# DS1077_breakout.net
KiCad netlist of a schematic drawn in EAGLE
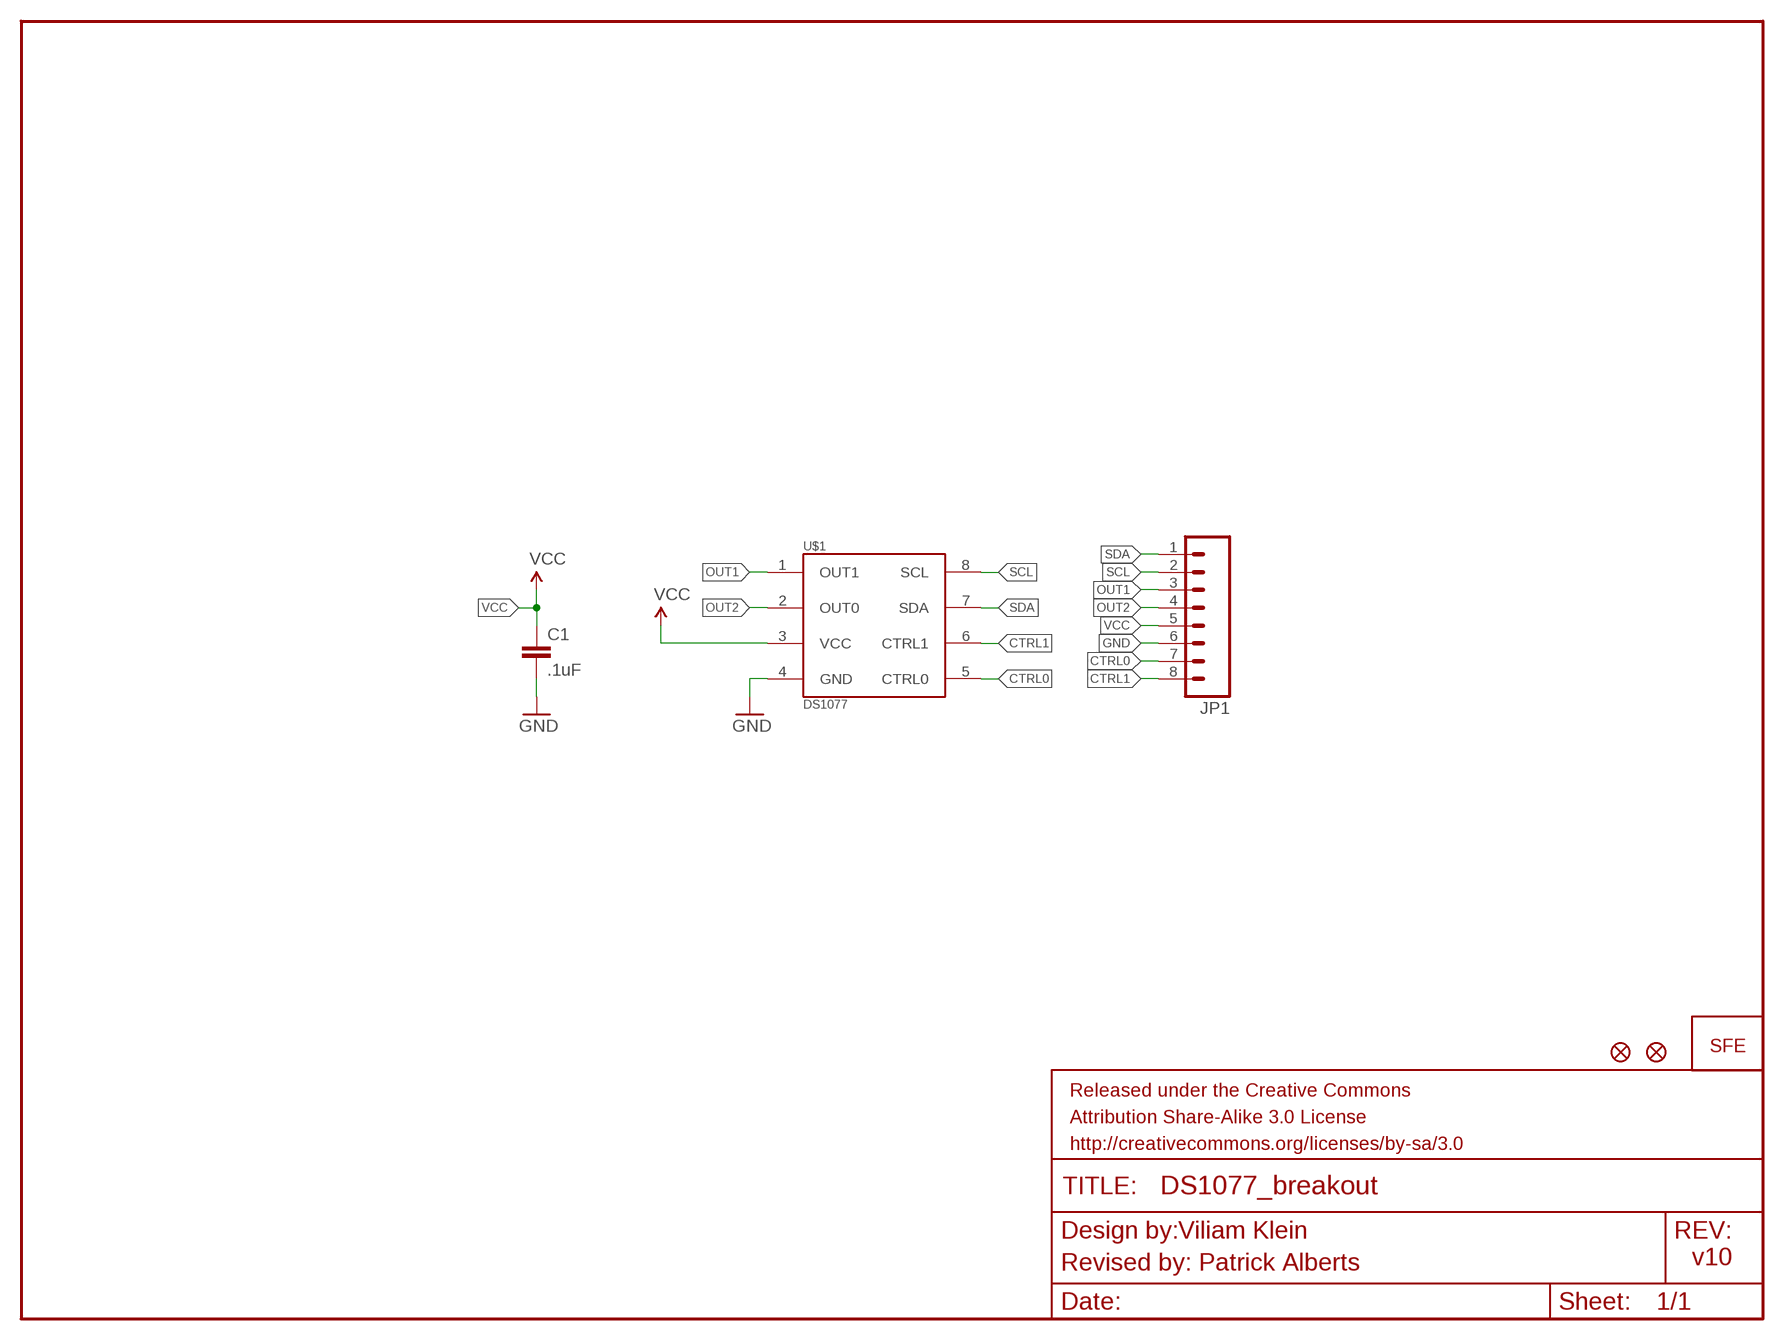
[diagram p0: schematic, sheet 1]

(export (version "E")
  (design (tool "Eeschema 10.0.6"))
  (components
    (comp (ref "C1")
      (value ".1uF")
      (footprint "eagle-import:0603")
      (libsource (lib "eagle-import") (part "CAP0603"))
    )
    (comp (ref "FRAME1")
      (value "FRAME-LETTER")
      (footprint "eagle-import:CREATIVE_COMMONS")
      (libsource (lib "eagle-import") (part "FRAME-LETTER"))
    )
    (comp (ref "JP1")
      (value "M081X08")
      (footprint "eagle-import:1X08")
      (libsource (lib "eagle-import") (part "M081X08"))
    )
    (comp (ref "U$1")
      (value "DS1077")
      (footprint "eagle-import:SO08")
      (libsource (lib "eagle-import") (part "DS1077"))
    )
    (comp (ref "U$2")
      (value "LOGO-SFESK")
      (footprint "eagle-import:SFE-LOGO-FLAME")
      (libsource (lib "eagle-import") (part "LOGO-SFESK"))
    )
    (comp (ref "U$3")
      (value "FIDUCIAL1X2")
      (footprint "eagle-import:FIDUCIAL-1X2")
      (libsource (lib "eagle-import") (part "FIDUCIAL1X2"))
    )
    (comp (ref "U$4")
      (value "FIDUCIAL1X2")
      (footprint "eagle-import:FIDUCIAL-1X2")
      (libsource (lib "eagle-import") (part "FIDUCIAL1X2"))
    )
  )
  (nets
    (net (code "1") (name "CTRL0") (class "Default")
      (node (ref "JP1") (pin "7") (pinfunction "7_7") (pintype "passive"))
      (node (ref "U$1") (pin "5") (pinfunction "CTRL0_5") (pintype "bidirectional"))
    )
    (net (code "2") (name "CTRL1") (class "Default")
      (node (ref "JP1") (pin "8") (pinfunction "8_8") (pintype "passive"))
      (node (ref "U$1") (pin "6") (pinfunction "CTRL1_6") (pintype "bidirectional"))
    )
    (net (code "3") (name "GND") (class "Default")
      (node (ref "C1") (pin "2") (pinfunction "2_2") (pintype "passive"))
      (node (ref "JP1") (pin "6") (pinfunction "6_6") (pintype "passive"))
      (node (ref "U$1") (pin "4") (pinfunction "GND_4") (pintype "bidirectional"))
    )
    (net (code "4") (name "OUT1") (class "Default")
      (node (ref "JP1") (pin "3") (pinfunction "3_3") (pintype "passive"))
      (node (ref "U$1") (pin "1") (pinfunction "OUT1_1") (pintype "bidirectional"))
    )
    (net (code "5") (name "OUT2") (class "Default")
      (node (ref "JP1") (pin "4") (pinfunction "4_4") (pintype "passive"))
      (node (ref "U$1") (pin "2") (pinfunction "OUT0_2") (pintype "bidirectional"))
    )
    (net (code "6") (name "SCL") (class "Default")
      (node (ref "JP1") (pin "2") (pinfunction "2_2") (pintype "passive"))
      (node (ref "U$1") (pin "8") (pinfunction "SCL_8") (pintype "bidirectional"))
    )
    (net (code "7") (name "SDA") (class "Default")
      (node (ref "JP1") (pin "1") (pinfunction "1_1") (pintype "passive"))
      (node (ref "U$1") (pin "7") (pinfunction "SDA_7") (pintype "bidirectional"))
    )
    (net (code "8") (name "VCC") (class "Default")
      (node (ref "C1") (pin "1") (pinfunction "1_1") (pintype "passive"))
      (node (ref "JP1") (pin "5") (pinfunction "5_5") (pintype "passive"))
      (node (ref "U$1") (pin "3") (pinfunction "VCC_3") (pintype "bidirectional"))
    )
  )
)
